# 4G.net
KiCad netlist of a schematic drawn in Altium Designer
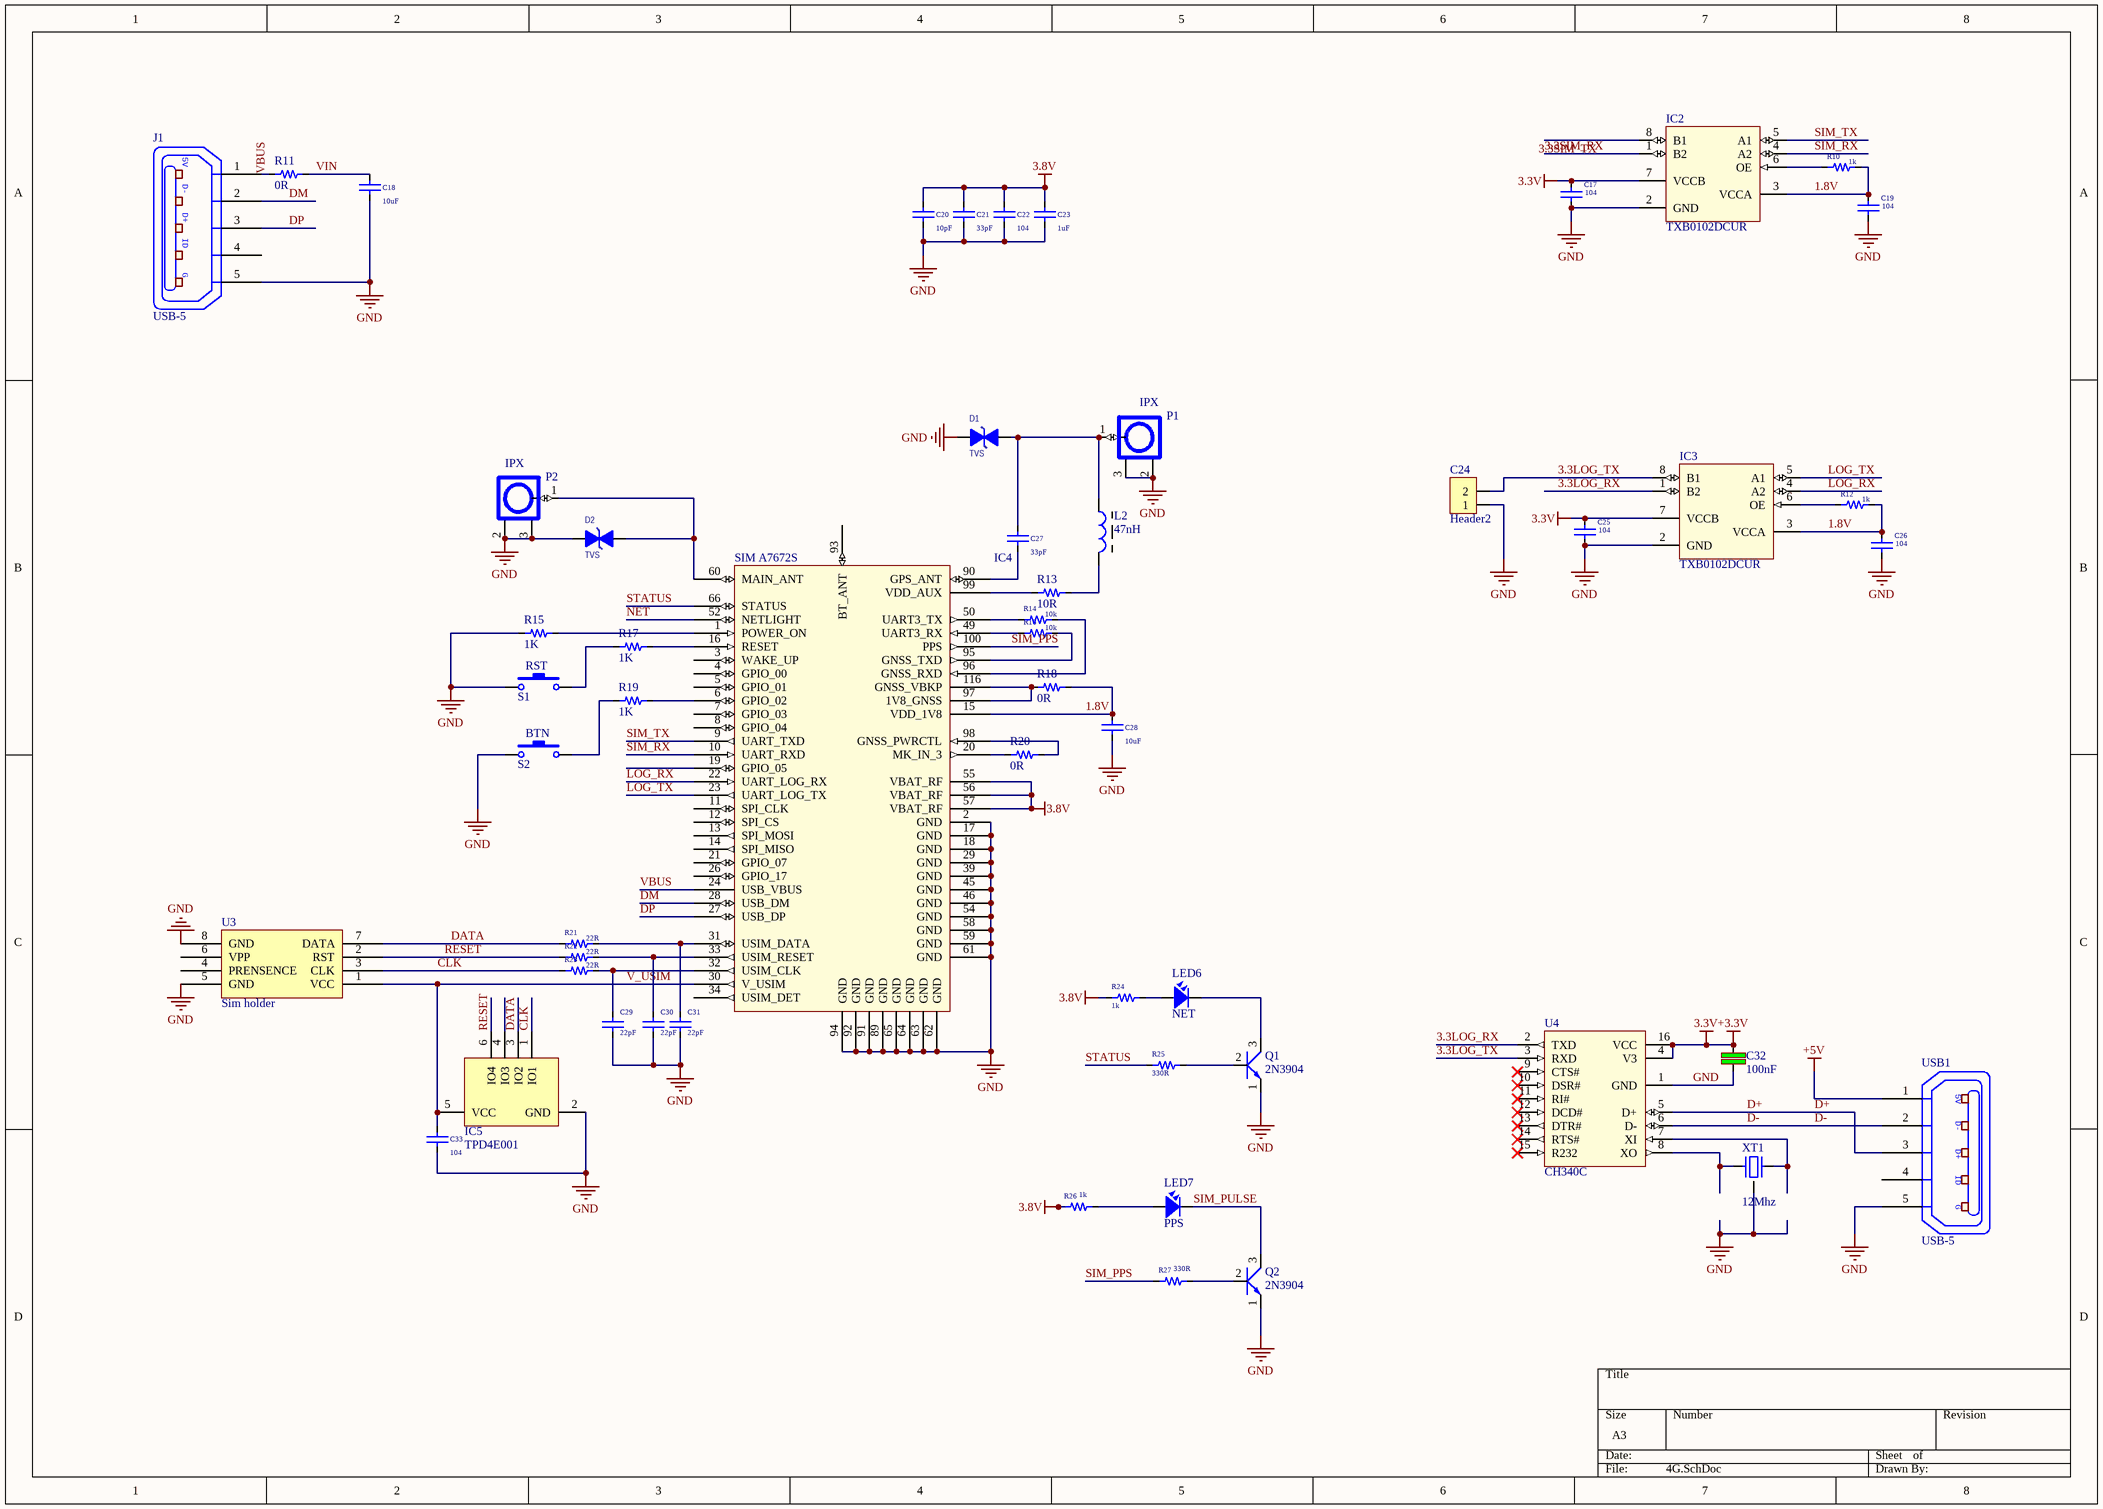
[diagram p0: 4G.SchDoc]

(export (version "E")
  (design (tool "Eeschema 10.0.6"))
  (components
    (comp (ref "C17")
      (value "104")
      (footprint "CAP_0603")
      (description "Capacitor")
      (fields (field (name "PUBLISHER") "Altium Limited"))
      (libsource (lib "My Library") (part "CapSMD"))
    )
    (comp (ref "C18")
      (value "10uF")
      (footprint "CAP_0603")
      (description "Capacitor")
      (fields (field (name "PUBLISHER") "Altium Limited"))
      (libsource (lib "My Library") (part "CapSMD"))
    )
    (comp (ref "C19")
      (value "104")
      (footprint "CAP_0603")
      (description "Capacitor")
      (fields (field (name "PUBLISHER") "Altium Limited"))
      (libsource (lib "My Library") (part "CapSMD"))
    )
    (comp (ref "C20")
      (value "10pF")
      (footprint "CAP_0603")
      (description "Capacitor")
      (fields (field (name "PUBLISHER") "Altium Limited"))
      (libsource (lib "My Library") (part "CapSMD"))
    )
    (comp (ref "C21")
      (value "33pF")
      (footprint "CAP_0603")
      (description "Capacitor")
      (fields (field (name "PUBLISHER") "Altium Limited"))
      (libsource (lib "My Library") (part "CapSMD"))
    )
    (comp (ref "C22")
      (value "104")
      (footprint "CAP_0603")
      (description "Capacitor")
      (fields (field (name "PUBLISHER") "Altium Limited"))
      (libsource (lib "My Library") (part "CapSMD"))
    )
    (comp (ref "C23")
      (value "1uF")
      (footprint "CAP_0603")
      (description "Capacitor")
      (fields (field (name "PUBLISHER") "Altium Limited"))
      (libsource (lib "My Library") (part "CapSMD"))
    )
    (comp (ref "C24")
      (value "Header2")
      (footprint "JP2")
      (description "Header IDC, 2 x 1 Pin Vertical 2.54mm Pitch (Non-Boxed, Male)")
      (fields
        (field (name "MANUFACTURER") "Würth Elektronik eiSos GmbH")
        (field (name "PARTNO") "613002143121")
        (field (name "CREATED BY") "Karrer Zheng")
      )
      (libsource (lib "My Library") (part "Header2"))
    )
    (comp (ref "C25")
      (value "104")
      (footprint "CAP_0603")
      (description "Capacitor")
      (fields (field (name "PUBLISHER") "Altium Limited"))
      (libsource (lib "My Library") (part "CapSMD"))
    )
    (comp (ref "C26")
      (value "104")
      (footprint "CAP_0603")
      (description "Capacitor")
      (fields (field (name "PUBLISHER") "Altium Limited"))
      (libsource (lib "My Library") (part "CapSMD"))
    )
    (comp (ref "C27")
      (value "33pF")
      (footprint "CAP_0603")
      (description "Capacitor")
      (fields (field (name "PUBLISHER") "Altium Limited"))
      (libsource (lib "My Library") (part "CapSMD"))
    )
    (comp (ref "C28")
      (value "10uF")
      (footprint "CAP_0603")
      (description "Capacitor")
      (fields (field (name "PUBLISHER") "Altium Limited"))
      (libsource (lib "My Library") (part "CapSMD"))
    )
    (comp (ref "C29")
      (value "22pF")
      (footprint "CAP_0603")
      (description "Capacitor")
      (fields (field (name "PUBLISHER") "Altium Limited"))
      (libsource (lib "My Library") (part "CapSMD"))
    )
    (comp (ref "C30")
      (value "22pF")
      (footprint "CAP_0603")
      (description "Capacitor")
      (fields (field (name "PUBLISHER") "Altium Limited"))
      (libsource (lib "My Library") (part "CapSMD"))
    )
    (comp (ref "C31")
      (value "22pF")
      (footprint "CAP_0603")
      (description "Capacitor")
      (fields (field (name "PUBLISHER") "Altium Limited"))
      (libsource (lib "My Library") (part "CapSMD"))
    )
    (comp (ref "C32")
      (value "100nF")
      (footprint "C-0805")
      (description "Cap SMD")
      (fields
        (field (name "MANUFACTURER") "Samsung Electro-Mechanics")
        (field (name "PART NUMBER") "CL21B104KBCNNWC")
      )
      (libsource (lib "Anh_Trung") (part "C"))
    )
    (comp (ref "C33")
      (value "104")
      (footprint "CAP_0603")
      (description "Capacitor")
      (fields (field (name "PUBLISHER") "Altium Limited"))
      (libsource (lib "My Library") (part "CapSMD"))
    )
    (comp (ref "D1")
      (value "TVS")
      (footprint "RES-SMD-0402")
      (description "TVS DIODE 4VWM 1005")
      (fields
        (field (name "MANUFACTURER") "Murata Electronics")
        (field (name "PART NUMBER") "LXES15AAA1-153")
      )
      (libsource (lib "My Library") (part "TVS"))
    )
    (comp (ref "D2")
      (value "TVS")
      (footprint "RES-SMD-0402")
      (description "TVS DIODE 4VWM 1005")
      (fields
        (field (name "MANUFACTURER") "Murata Electronics")
        (field (name "PART NUMBER") "LXES15AAA1-153")
      )
      (libsource (lib "My Library") (part "TVS"))
    )
    (comp (ref "IC2")
      (value "TXB0102DCUR")
      (footprint "TXB0102DCUR")
      (description "IC TRNSLTR BIDIRECTIONAL US8")
      (fields (field (name "MANUFACTURER") "Texas Instruments"))
      (libsource (lib "My Library") (part "TXB0102DCUR"))
    )
    (comp (ref "IC3")
      (value "TXB0102DCUR")
      (footprint "TXB0102DCUR")
      (description "IC TRNSLTR BIDIRECTIONAL US8")
      (fields (field (name "MANUFACTURER") "Texas Instruments"))
      (libsource (lib "My Library") (part "TXB0102DCUR"))
    )
    (comp (ref "IC4")
      (value "SIM A7672S")
      (footprint "A7672S")
      (description "SIM A7672S-CAT-M1")
      (libsource (lib "My Library") (part "SIM A7672S"))
    )
    (comp (ref "IC5")
      (value "TPD4E001")
      (footprint "TPD4E001")
      (fields (field (name "MANUFACTURER") "Texas Instruments") (field (name "PART NUMBER") "TPD4E001RDBVR"))
      (libsource (lib "My Library") (part "TPD4E001_1"))
    )
    (comp (ref "J1")
      (value "USB-5")
      (footprint "USB-M1")
      (fields (field (name "MANUFACTURER") "FCI"))
      (libsource (lib "Anh_Trung") (part "USB-5"))
    )
    (comp (ref "L2")
      (value "47nH")
      (footprint "RES-SMD-0603")
      (description "FIXED IND 47NH 300MA 700MOHM SMD")
      (fields (field (name "MANUFACTURER") "Taiyo Yuden") (field (name "PART NUMBER") "HK160847NJ-T"))
      (libsource (lib "Anh_Trung") (part "Inductor Ferit"))
    )
    (comp (ref "LED6")
      (value "NET")
      (footprint "LED-0805-Blue")
      (description "LED Single colour Green and Red")
      (libsource (lib "Main") (part "LED"))
    )
    (comp (ref "LED7")
      (value "PPS")
      (footprint "LED-0805-Blue")
      (description "LED Single colour Green and Red")
      (libsource (lib "Main") (part "LED"))
    )
    (comp (ref "P1")
      (value "IPX")
      (footprint "IPXS")
      (description "Antenna GSM GPS")
      (fields
        (field (name "MANUFACTURER") "TE Connectivity AMP Connectors")
        (field (name "PART NUMBER") "2334884-1")
      )
      (libsource (lib "Anh_Trung") (part "IPXSx66"))
    )
    (comp (ref "P2")
      (value "IPX")
      (footprint "IPXS")
      (description "Antenna GSM GPS")
      (fields
        (field (name "MANUFACTURER") "TE Connectivity AMP Connectors")
        (field (name "PART NUMBER") "2334884-1")
      )
      (libsource (lib "") (part "IPXSx66_1"))
    )
    (comp (ref "Q1")
      (value "2N3904")
      (footprint "SOT23C")
      (description "NPN 600mW, ECB")
      (libsource (lib "Main") (part "2N904"))
    )
    (comp (ref "Q2")
      (value "2N3904")
      (footprint "SOT23C")
      (description "NPN 600mW, ECB")
      (libsource (lib "Main") (part "2N904"))
    )
    (comp (ref "R10")
      (value "1k")
      (footprint "RES-SMD-0603")
      (description "Resistor")
      (fields
        (field (name "MANUFACTURER") "Generic Components")
        (field (name "PUBLISHER") "Altium Hobart Technology Centre")
      )
      (libsource (lib "My Library") (part "Resistor - SMD"))
    )
    (comp (ref "R11")
      (value "0R")
      (footprint "RES-SMD-0603")
      (description "Resistor")
      (fields
        (field (name "MANUFACTURER") "Generic Components")
        (field (name "PUBLISHER") "Altium Hobart Technology Centre")
      )
      (libsource (lib "My Library") (part "Resistor - SMD"))
    )
    (comp (ref "R12")
      (value "1k")
      (footprint "RES-SMD-0603")
      (description "Resistor")
      (fields
        (field (name "MANUFACTURER") "Generic Components")
        (field (name "PUBLISHER") "Altium Hobart Technology Centre")
      )
      (libsource (lib "My Library") (part "Resistor - SMD"))
    )
    (comp (ref "R13")
      (value "10R")
      (footprint "RES-SMD-0603")
      (description "Resistor")
      (fields
        (field (name "MANUFACTURER") "Generic Components")
        (field (name "PUBLISHER") "Altium Hobart Technology Centre")
      )
      (libsource (lib "My Library") (part "Resistor - SMD"))
    )
    (comp (ref "R14")
      (value "10k")
      (footprint "RES-SMD-0603")
      (description "Resistor")
      (fields
        (field (name "MANUFACTURER") "Generic Components")
        (field (name "PUBLISHER") "Altium Hobart Technology Centre")
      )
      (libsource (lib "My Library") (part "Resistor - SMD"))
    )
    (comp (ref "R15")
      (value "1K")
      (footprint "RES-SMD-0603")
      (description "Resistor")
      (fields
        (field (name "MANUFACTURER") "Generic Components")
        (field (name "PUBLISHER") "Altium Hobart Technology Centre")
      )
      (libsource (lib "My Library") (part "Resistor - SMD"))
    )
    (comp (ref "R16")
      (value "10k")
      (footprint "RES-SMD-0603")
      (description "Resistor")
      (fields
        (field (name "MANUFACTURER") "Generic Components")
        (field (name "PUBLISHER") "Altium Hobart Technology Centre")
      )
      (libsource (lib "My Library") (part "Resistor - SMD"))
    )
    (comp (ref "R17")
      (value "1K")
      (footprint "RES-SMD-0603")
      (description "Resistor")
      (fields
        (field (name "MANUFACTURER") "Generic Components")
        (field (name "PUBLISHER") "Altium Hobart Technology Centre")
      )
      (libsource (lib "My Library") (part "Resistor - SMD"))
    )
    (comp (ref "R18")
      (value "0R")
      (footprint "RES-SMD-0603")
      (description "Resistor")
      (fields
        (field (name "MANUFACTURER") "Generic Components")
        (field (name "PUBLISHER") "Altium Hobart Technology Centre")
      )
      (libsource (lib "My Library") (part "Resistor - SMD"))
    )
    (comp (ref "R19")
      (value "1K")
      (footprint "RES-SMD-0603")
      (description "Resistor")
      (fields
        (field (name "MANUFACTURER") "Generic Components")
        (field (name "PUBLISHER") "Altium Hobart Technology Centre")
      )
      (libsource (lib "My Library") (part "Resistor - SMD"))
    )
    (comp (ref "R20")
      (value "0R")
      (footprint "RES-SMD-0603")
      (description "Resistor")
      (fields
        (field (name "MANUFACTURER") "Generic Components")
        (field (name "PUBLISHER") "Altium Hobart Technology Centre")
      )
      (libsource (lib "My Library") (part "Resistor - SMD"))
    )
    (comp (ref "R21")
      (value "22R")
      (footprint "RES-SMD-0603")
      (description "Resistor")
      (fields
        (field (name "MANUFACTURER") "Generic Components")
        (field (name "PUBLISHER") "Altium Hobart Technology Centre")
      )
      (libsource (lib "My Library") (part "Resistor - SMD"))
    )
    (comp (ref "R22")
      (value "22R")
      (footprint "RES-SMD-0603")
      (description "Resistor")
      (fields
        (field (name "MANUFACTURER") "Generic Components")
        (field (name "PUBLISHER") "Altium Hobart Technology Centre")
      )
      (libsource (lib "My Library") (part "Resistor - SMD"))
    )
    (comp (ref "R23")
      (value "22R")
      (footprint "RES-SMD-0603")
      (description "Resistor")
      (fields
        (field (name "MANUFACTURER") "Generic Components")
        (field (name "PUBLISHER") "Altium Hobart Technology Centre")
      )
      (libsource (lib "My Library") (part "Resistor - SMD"))
    )
    (comp (ref "R24")
      (value "1k")
      (footprint "RES-SMD-0603")
      (description "Resistor")
      (fields
        (field (name "MANUFACTURER") "Generic Components")
        (field (name "PUBLISHER") "Altium Hobart Technology Centre")
      )
      (libsource (lib "My Library") (part "Resistor - SMD"))
    )
    (comp (ref "R25")
      (value "330R")
      (footprint "RES-SMD-0603")
      (description "Resistor")
      (fields
        (field (name "MANUFACTURER") "Generic Components")
        (field (name "PUBLISHER") "Altium Hobart Technology Centre")
      )
      (libsource (lib "My Library") (part "Resistor - SMD"))
    )
    (comp (ref "R26")
      (value "1k")
      (footprint "RES-SMD-0603")
      (description "Resistor")
      (fields
        (field (name "MANUFACTURER") "Generic Components")
        (field (name "PUBLISHER") "Altium Hobart Technology Centre")
      )
      (libsource (lib "My Library") (part "Resistor - SMD"))
    )
    (comp (ref "R27")
      (value "330R")
      (footprint "RES-SMD-0603")
      (description "Resistor")
      (fields
        (field (name "MANUFACTURER") "Generic Components")
        (field (name "PUBLISHER") "Altium Hobart Technology Centre")
      )
      (libsource (lib "My Library") (part "Resistor - SMD"))
    )
    (comp (ref "S1")
      (value "RST")
      (footprint "SW-SMD")
      (description "Switch")
      (fields (field (name "PUBLISHER") "Altium Limited"))
      (libsource (lib "My Library") (part "SW-SMD"))
    )
    (comp (ref "S2")
      (value "BTN")
      (footprint "SW-SMD")
      (description "Switch")
      (fields (field (name "PUBLISHER") "Altium Limited"))
      (libsource (lib "My Library") (part "SW-SMD"))
    )
    (comp (ref "U3")
      (value "Sim holder")
      (footprint "sim_holder_micro")
      (libsource (lib "Anh_Trung") (part "Component_1"))
    )
    (comp (ref "U4")
      (value "CH340C")
      (footprint "SOP-16")
      (description "USB to UART Interface")
      (fields (field (name "MANUFACTURER") "WCH") (field (name "PART NUMBER") "CH340G"))
      (libsource (lib "Anh_Trung") (part "CH340G"))
    )
    (comp (ref "USB1")
      (value "USB-5")
      (footprint "USB-M1")
      (fields (field (name "MANUFACTURER") "FCI"))
      (libsource (lib "") (part "USB-5_1"))
    )
    (comp (ref "XT1")
      (value "12Mhz")
      (footprint "XT32-3")
      (description "Crystal 32,768kHz for timer real")
      (libsource (lib "Anh_Trung") (part "XT32k"))
    )
  )
  (nets
    (net (code "1") (name "+3.3V") (class "Default")
      (node (ref "C17") (pin "2") (pinfunction "2_2") (pintype "passive"))
      (node (ref "C25") (pin "2") (pinfunction "2_2") (pintype "passive"))
      (node (ref "C32") (pin "2") (pinfunction "2_2") (pintype "passive"))
      (node (ref "IC2") (pin "7") (pinfunction "VCCB_7") (pintype "power_in"))
      (node (ref "IC3") (pin "7") (pinfunction "VCCB_7") (pintype "power_in"))
      (node (ref "U4") (pin "16") (pinfunction "VCC_16") (pintype "power_in"))
      (node (ref "U4") (pin "4") (pinfunction "V3_4") (pintype "passive"))
    )
    (net (code "2") (name "+5V") (class "Default")
      (node (ref "USB1") (pin "1") (pinfunction "P1_1") (pintype "passive"))
    )
    (net (code "3") (name "/1.8V") (class "Default")
      (node (ref "C19") (pin "2") (pinfunction "2_2") (pintype "passive"))
      (node (ref "C26") (pin "2") (pinfunction "2_2") (pintype "passive"))
      (node (ref "C28") (pin "2") (pinfunction "2_2") (pintype "passive"))
      (node (ref "IC2") (pin "3") (pinfunction "VCCA_3") (pintype "power_in"))
      (node (ref "IC3") (pin "3") (pinfunction "VCCA_3") (pintype "power_in"))
      (node (ref "IC4") (pin "15") (pinfunction "VDD_1V8_15") (pintype "passive"))
      (node (ref "R10") (pin "1") (pinfunction "1_1") (pintype "passive"))
      (node (ref "R12") (pin "1") (pinfunction "1_1") (pintype "passive"))
      (node (ref "R18") (pin "2") (pinfunction "2_2") (pintype "passive"))
    )
    (net (code "4") (name "/3.3LOG_RX") (class "Default")
      (node (ref "IC3") (pin "1") (pinfunction "B2_1") (pintype "bidirectional"))
      (node (ref "U4") (pin "2") (pinfunction "TXD_2") (pintype "output"))
    )
    (net (code "5") (name "/3.3LOG_TX") (class "Default")
      (node (ref "C24") (pin "2") (pinfunction "2_2") (pintype "passive"))
      (node (ref "IC3") (pin "8") (pinfunction "B1_8") (pintype "bidirectional"))
      (node (ref "U4") (pin "3") (pinfunction "RXD_3") (pintype "input"))
    )
    (net (code "6") (name "/3.3SIM_RX") (class "Default")
      (node (ref "IC2") (pin "1") (pinfunction "B2_1") (pintype "bidirectional"))
    )
    (net (code "7") (name "/3.3SIM_TX") (class "Default")
      (node (ref "IC2") (pin "8") (pinfunction "B1_8") (pintype "bidirectional"))
    )
    (net (code "8") (name "/CLK") (class "Default")
      (node (ref "IC5") (pin "1") (pinfunction "IO1_1") (pintype "passive"))
      (node (ref "R23") (pin "2") (pinfunction "2_2") (pintype "passive"))
      (node (ref "U3") (pin "3") (pinfunction "CLK_3") (pintype "passive"))
    )
    (net (code "9") (name "/D+") (class "Default")
      (node (ref "U4") (pin "5") (pinfunction "D+_5") (pintype "bidirectional"))
      (node (ref "USB1") (pin "3") (pinfunction "P3_3") (pintype "passive"))
    )
    (net (code "10") (name "/D-") (class "Default")
      (node (ref "U4") (pin "6") (pinfunction "D-_6") (pintype "bidirectional"))
      (node (ref "USB1") (pin "2") (pinfunction "P2_2") (pintype "passive"))
    )
    (net (code "11") (name "/DATA") (class "Default")
      (node (ref "IC5") (pin "3") (pinfunction "IO2_3") (pintype "passive"))
      (node (ref "R21") (pin "2") (pinfunction "2_2") (pintype "passive"))
      (node (ref "U3") (pin "7") (pinfunction "DATA_7") (pintype "passive"))
    )
    (net (code "12") (name "/DM") (class "Default")
      (node (ref "IC4") (pin "28") (pinfunction "USB_DM_28") (pintype "bidirectional"))
      (node (ref "J1") (pin "2") (pinfunction "P2_2") (pintype "passive"))
    )
    (net (code "13") (name "/DP") (class "Default")
      (node (ref "IC4") (pin "27") (pinfunction "USB_DP_27") (pintype "bidirectional"))
      (node (ref "J1") (pin "3") (pinfunction "P3_3") (pintype "passive"))
    )
    (net (code "14") (name "/LOG_RX") (class "Default")
      (node (ref "IC3") (pin "4") (pinfunction "A2_4") (pintype "bidirectional"))
      (node (ref "IC4") (pin "22") (pinfunction "UART_LOG_RX_22") (pintype "input"))
    )
    (net (code "15") (name "/LOG_TX") (class "Default")
      (node (ref "IC3") (pin "5") (pinfunction "A1_5") (pintype "bidirectional"))
      (node (ref "IC4") (pin "23") (pinfunction "UART_LOG_TX_23") (pintype "output"))
    )
    (net (code "16") (name "/NET") (class "Default")
      (node (ref "IC4") (pin "52") (pinfunction "NETLIGHT_52") (pintype "bidirectional"))
    )
    (net (code "17") (name "/RESET") (class "Default")
      (node (ref "IC5") (pin "6") (pinfunction "IO4_6") (pintype "passive"))
      (node (ref "R22") (pin "2") (pinfunction "2_2") (pintype "passive"))
      (node (ref "U3") (pin "2") (pinfunction "RST_2") (pintype "passive"))
    )
    (net (code "18") (name "/SIM_PPS") (class "Default")
      (node (ref "IC4") (pin "100") (pinfunction "PPS_100") (pintype "output"))
      (node (ref "R27") (pin "2") (pinfunction "2_2") (pintype "passive"))
    )
    (net (code "19") (name "/SIM_PULSE") (class "Default")
      (node (ref "LED7") (pin "2") (pinfunction "2_2") (pintype "passive"))
      (node (ref "Q2") (pin "3") (pinfunction "C_3") (pintype "passive"))
    )
    (net (code "20") (name "/SIM_RX") (class "Default")
      (node (ref "IC2") (pin "4") (pinfunction "A2_4") (pintype "bidirectional"))
      (node (ref "IC4") (pin "10") (pinfunction "UART_RXD_10") (pintype "input"))
    )
    (net (code "21") (name "/SIM_TX") (class "Default")
      (node (ref "IC2") (pin "5") (pinfunction "A1_5") (pintype "bidirectional"))
      (node (ref "IC4") (pin "9") (pinfunction "UART_TXD_9") (pintype "output"))
    )
    (net (code "22") (name "/STATUS") (class "Default")
      (node (ref "IC4") (pin "66") (pinfunction "STATUS_66") (pintype "bidirectional"))
      (node (ref "R25") (pin "2") (pinfunction "2_2") (pintype "passive"))
    )
    (net (code "23") (name "/VBUS") (class "Default")
      (node (ref "IC4") (pin "24") (pinfunction "USB_VBUS_24") (pintype "passive"))
      (node (ref "J1") (pin "1") (pinfunction "P1_1") (pintype "passive"))
      (node (ref "R11") (pin "1") (pinfunction "1_1") (pintype "passive"))
    )
    (net (code "24") (name "/VIN") (class "Default")
      (node (ref "C18") (pin "2") (pinfunction "2_2") (pintype "passive"))
      (node (ref "R11") (pin "2") (pinfunction "2_2") (pintype "passive"))
    )
    (net (code "25") (name "/V_USIM") (class "Default")
      (node (ref "C33") (pin "2") (pinfunction "2_2") (pintype "passive"))
      (node (ref "IC4") (pin "30") (pinfunction "V_USIM_30") (pintype "output"))
      (node (ref "IC5") (pin "5") (pinfunction "VCC_5") (pintype "passive"))
      (node (ref "U3") (pin "1") (pinfunction "VCC_1") (pintype "passive"))
    )
    (net (code "26") (name "3.8V") (class "Default")
      (node (ref "C20") (pin "2") (pinfunction "2_2") (pintype "passive"))
      (node (ref "C21") (pin "2") (pinfunction "2_2") (pintype "passive"))
      (node (ref "C22") (pin "2") (pinfunction "2_2") (pintype "passive"))
      (node (ref "C23") (pin "2") (pinfunction "2_2") (pintype "passive"))
      (node (ref "IC4") (pin "55") (pinfunction "VBAT_RF_55") (pintype "passive"))
      (node (ref "IC4") (pin "56") (pinfunction "VBAT_RF_56") (pintype "passive"))
      (node (ref "IC4") (pin "57") (pinfunction "VBAT_RF_57") (pintype "passive"))
      (node (ref "R24") (pin "2") (pinfunction "2_2") (pintype "passive"))
      (node (ref "R26") (pin "2") (pinfunction "2_2") (pintype "passive"))
    )
    (net (code "27") (name "GND") (class "Default")
      (node (ref "C17") (pin "1") (pinfunction "1_1") (pintype "passive"))
      (node (ref "C18") (pin "1") (pinfunction "1_1") (pintype "passive"))
      (node (ref "C19") (pin "1") (pinfunction "1_1") (pintype "passive"))
      (node (ref "C20") (pin "1") (pinfunction "1_1") (pintype "passive"))
      (node (ref "C21") (pin "1") (pinfunction "1_1") (pintype "passive"))
      (node (ref "C22") (pin "1") (pinfunction "1_1") (pintype "passive"))
      (node (ref "C23") (pin "1") (pinfunction "1_1") (pintype "passive"))
      (node (ref "C24") (pin "1") (pinfunction "1_1") (pintype "passive"))
      (node (ref "C25") (pin "1") (pinfunction "1_1") (pintype "passive"))
      (node (ref "C26") (pin "1") (pinfunction "1_1") (pintype "passive"))
      (node (ref "C28") (pin "1") (pinfunction "1_1") (pintype "passive"))
      (node (ref "C29") (pin "1") (pinfunction "1_1") (pintype "passive"))
      (node (ref "C30") (pin "1") (pinfunction "1_1") (pintype "passive"))
      (node (ref "C31") (pin "1") (pinfunction "1_1") (pintype "passive"))
      (node (ref "C32") (pin "1") (pinfunction "1_1") (pintype "passive"))
      (node (ref "C33") (pin "1") (pinfunction "1_1") (pintype "passive"))
      (node (ref "D1") (pin "2") (pinfunction "K_2") (pintype "passive"))
      (node (ref "D2") (pin "2") (pinfunction "K_2") (pintype "passive"))
      (node (ref "IC2") (pin "2") (pinfunction "GND_2") (pintype "power_in"))
      (node (ref "IC3") (pin "2") (pinfunction "GND_2") (pintype "power_in"))
      (node (ref "IC4") (pin "17") (pinfunction "GND_17") (pintype "passive"))
      (node (ref "IC4") (pin "18") (pinfunction "GND_18") (pintype "passive"))
      (node (ref "IC4") (pin "2") (pinfunction "GND_2") (pintype "passive"))
      (node (ref "IC4") (pin "29") (pinfunction "GND_29") (pintype "passive"))
      (node (ref "IC4") (pin "39") (pinfunction "GND_39") (pintype "passive"))
      (node (ref "IC4") (pin "45") (pinfunction "GND_45") (pintype "passive"))
      (node (ref "IC4") (pin "46") (pinfunction "GND_46") (pintype "passive"))
      (node (ref "IC4") (pin "54") (pinfunction "GND_54") (pintype "passive"))
      (node (ref "IC4") (pin "58") (pinfunction "GND_58") (pintype "passive"))
      (node (ref "IC4") (pin "59") (pinfunction "GND_59") (pintype "passive"))
      (node (ref "IC4") (pin "61") (pinfunction "GND_61") (pintype "passive"))
      (node (ref "IC4") (pin "62") (pinfunction "GND_62") (pintype "passive"))
      (node (ref "IC4") (pin "63") (pinfunction "GND_63") (pintype "passive"))
      (node (ref "IC4") (pin "64") (pinfunction "GND_64") (pintype "passive"))
      (node (ref "IC4") (pin "65") (pinfunction "GND_65") (pintype "passive"))
      (node (ref "IC4") (pin "89") (pinfunction "GND_89") (pintype "passive"))
      (node (ref "IC4") (pin "91") (pinfunction "GND_91") (pintype "passive"))
      (node (ref "IC4") (pin "92") (pinfunction "GND_92") (pintype "passive"))
      (node (ref "IC4") (pin "94") (pinfunction "GND_94") (pintype "passive"))
      (node (ref "IC5") (pin "2") (pinfunction "GND_2") (pintype "passive"))
      (node (ref "J1") (pin "5") (pinfunction "P5_5") (pintype "passive"))
      (node (ref "P1") (pin "2") (pintype "passive"))
      (node (ref "P1") (pin "3") (pintype "passive"))
      (node (ref "P2") (pin "2") (pintype "passive"))
      (node (ref "P2") (pin "3") (pintype "passive"))
      (node (ref "Q1") (pin "1") (pinfunction "E_1") (pintype "passive"))
      (node (ref "Q2") (pin "1") (pinfunction "E_1") (pintype "passive"))
      (node (ref "R15") (pin "1") (pinfunction "1_1") (pintype "passive"))
      (node (ref "S1") (pin "1") (pinfunction "1_1") (pintype "passive"))
      (node (ref "S2") (pin "1") (pinfunction "1_1") (pintype "passive"))
      (node (ref "U3") (pin "5") (pinfunction "GND_5") (pintype "passive"))
      (node (ref "U3") (pin "8") (pinfunction "GND_8") (pintype "passive"))
      (node (ref "U4") (pin "1") (pinfunction "GND_1") (pintype "passive"))
      (node (ref "USB1") (pin "5") (pinfunction "P5_5") (pintype "passive"))
      (node (ref "XT1") (pin "3") (pinfunction "3_3") (pintype "passive"))
    )
    (net (code "28") (name "Net-(D1-A)") (class "Default")
      (node (ref "C27") (pin "2") (pinfunction "2_2") (pintype "passive"))
      (node (ref "D1") (pin "1") (pinfunction "A_1") (pintype "passive"))
      (node (ref "L2") (pin "1") (pinfunction "1_1") (pintype "passive"))
      (node (ref "P1") (pin "1") (pintype "bidirectional"))
    )
    (net (code "29") (name "Net-(D2-A)") (class "Default")
      (node (ref "D2") (pin "1") (pinfunction "A_1") (pintype "passive"))
      (node (ref "IC4") (pin "60") (pinfunction "MAIN_ANT_60") (pintype "bidirectional"))
      (node (ref "P2") (pin "1") (pintype "bidirectional"))
    )
    (net (code "30") (name "Net-(IC2-OE)") (class "Default")
      (node (ref "IC2") (pin "6") (pinfunction "OE_6") (pintype "input"))
      (node (ref "R10") (pin "2") (pinfunction "2_2") (pintype "passive"))
    )
    (net (code "31") (name "Net-(IC3-OE)") (class "Default")
      (node (ref "IC3") (pin "6") (pinfunction "OE_6") (pintype "input"))
      (node (ref "R12") (pin "2") (pinfunction "2_2") (pintype "passive"))
    )
    (net (code "32") (name "Net-(IC4-1V8_GNSS)") (class "Default")
      (node (ref "IC4") (pin "116") (pinfunction "GNSS_VBKP_116") (pintype "passive"))
      (node (ref "IC4") (pin "97") (pinfunction "1V8_GNSS_97") (pintype "passive"))
      (node (ref "R18") (pin "1") (pinfunction "1_1") (pintype "passive"))
    )
    (net (code "33") (name "Net-(IC4-GNSS_PWRCTL)") (class "Default")
      (node (ref "IC4") (pin "98") (pinfunction "GNSS_PWRCTL_98") (pintype "input"))
      (node (ref "R20") (pin "2") (pinfunction "2_2") (pintype "passive"))
    )
    (net (code "34") (name "Net-(IC4-GNSS_RXD)") (class "Default")
      (node (ref "IC4") (pin "96") (pinfunction "GNSS_RXD_96") (pintype "input"))
      (node (ref "R14") (pin "1") (pinfunction "1_1") (pintype "passive"))
    )
    (net (code "35") (name "Net-(IC4-GNSS_TXD)") (class "Default")
      (node (ref "IC4") (pin "95") (pinfunction "GNSS_TXD_95") (pintype "output"))
      (node (ref "R16") (pin "1") (pinfunction "1_1") (pintype "passive"))
    )
    (net (code "36") (name "Net-(IC4-GPIO_02)") (class "Default")
      (node (ref "IC4") (pin "6") (pinfunction "GPIO_02_6") (pintype "bidirectional"))
      (node (ref "R19") (pin "1") (pinfunction "1_1") (pintype "passive"))
    )
    (net (code "37") (name "Net-(IC4-GPS_ANT)") (class "Default")
      (node (ref "C27") (pin "1") (pinfunction "1_1") (pintype "passive"))
      (node (ref "IC4") (pin "90") (pinfunction "GPS_ANT_90") (pintype "bidirectional"))
    )
    (net (code "38") (name "Net-(IC4-MK_IN_3)") (class "Default")
      (node (ref "IC4") (pin "20") (pinfunction "MK_IN_3_20") (pintype "output"))
      (node (ref "R20") (pin "1") (pinfunction "1_1") (pintype "passive"))
    )
    (net (code "39") (name "Net-(IC4-POWER_ON)") (class "Default")
      (node (ref "IC4") (pin "1") (pinfunction "POWER_ON_1") (pintype "input"))
      (node (ref "R15") (pin "2") (pinfunction "2_2") (pintype "passive"))
    )
    (net (code "40") (name "Net-(IC4-RESET)") (class "Default")
      (node (ref "IC4") (pin "16") (pinfunction "RESET_16") (pintype "input"))
      (node (ref "R17") (pin "2") (pinfunction "2_2") (pintype "passive"))
    )
    (net (code "41") (name "Net-(IC4-UART3_RX)") (class "Default")
      (node (ref "IC4") (pin "49") (pinfunction "UART3_RX_49") (pintype "input"))
      (node (ref "R16") (pin "2") (pinfunction "2_2") (pintype "passive"))
    )
    (net (code "42") (name "Net-(IC4-UART3_TX)") (class "Default")
      (node (ref "IC4") (pin "50") (pinfunction "UART3_TX_50") (pintype "output"))
      (node (ref "R14") (pin "2") (pinfunction "2_2") (pintype "passive"))
    )
    (net (code "43") (name "Net-(IC4-USIM_CLK)") (class "Default")
      (node (ref "C29") (pin "2") (pinfunction "2_2") (pintype "passive"))
      (node (ref "IC4") (pin "32") (pinfunction "USIM_CLK_32") (pintype "output"))
      (node (ref "R23") (pin "1") (pinfunction "1_1") (pintype "passive"))
    )
    (net (code "44") (name "Net-(IC4-USIM_DATA)") (class "Default")
      (node (ref "C31") (pin "2") (pinfunction "2_2") (pintype "passive"))
      (node (ref "IC4") (pin "31") (pinfunction "USIM_DATA_31") (pintype "bidirectional"))
      (node (ref "R21") (pin "1") (pinfunction "1_1") (pintype "passive"))
    )
    (net (code "45") (name "Net-(IC4-USIM_RESET)") (class "Default")
      (node (ref "C30") (pin "2") (pinfunction "2_2") (pintype "passive"))
      (node (ref "IC4") (pin "33") (pinfunction "USIM_RESET_33") (pintype "output"))
      (node (ref "R22") (pin "1") (pinfunction "1_1") (pintype "passive"))
    )
    (net (code "46") (name "Net-(IC4-VDD_AUX)") (class "Default")
      (node (ref "IC4") (pin "99") (pinfunction "VDD_AUX_99") (pintype "passive"))
      (node (ref "R13") (pin "1") (pinfunction "1_1") (pintype "passive"))
    )
    (net (code "47") (name "Net-(L2-Pad2)") (class "Default")
      (node (ref "L2") (pin "2") (pinfunction "2_2") (pintype "passive"))
      (node (ref "R13") (pin "2") (pinfunction "2_2") (pintype "passive"))
    )
    (net (code "48") (name "Net-(LED6-Pad1)") (class "Default")
      (node (ref "LED6") (pin "1") (pinfunction "1_1") (pintype "passive"))
      (node (ref "R24") (pin "1") (pinfunction "1_1") (pintype "passive"))
    )
    (net (code "49") (name "Net-(LED7-Pad1)") (class "Default")
      (node (ref "LED7") (pin "1") (pinfunction "1_1") (pintype "passive"))
      (node (ref "R26") (pin "1") (pinfunction "1_1") (pintype "passive"))
    )
    (net (code "50") (name "Net-(Q1-B)") (class "Default")
      (node (ref "Q1") (pin "2") (pinfunction "B_2") (pintype "passive"))
      (node (ref "R25") (pin "1") (pinfunction "1_1") (pintype "passive"))
    )
    (net (code "51") (name "Net-(Q1-C)") (class "Default")
      (node (ref "LED6") (pin "2") (pinfunction "2_2") (pintype "passive"))
      (node (ref "Q1") (pin "3") (pinfunction "C_3") (pintype "passive"))
    )
    (net (code "52") (name "Net-(Q2-B)") (class "Default")
      (node (ref "Q2") (pin "2") (pinfunction "B_2") (pintype "passive"))
      (node (ref "R27") (pin "1") (pinfunction "1_1") (pintype "passive"))
    )
    (net (code "53") (name "Net-(R17-Pad1)") (class "Default")
      (node (ref "R17") (pin "1") (pinfunction "1_1") (pintype "passive"))
      (node (ref "S1") (pin "2") (pinfunction "2_2") (pintype "passive"))
    )
    (net (code "54") (name "Net-(R19-Pad2)") (class "Default")
      (node (ref "R19") (pin "2") (pinfunction "2_2") (pintype "passive"))
      (node (ref "S2") (pin "2") (pinfunction "2_2") (pintype "passive"))
    )
    (net (code "55") (name "Net-(U4-XI)") (class "Default")
      (node (ref "U4") (pin "7") (pinfunction "XI_7") (pintype "input"))
      (node (ref "XT1") (pin "2") (pinfunction "2_2") (pintype "passive"))
    )
    (net (code "56") (name "Net-(U4-XO)") (class "Default")
      (node (ref "U4") (pin "8") (pinfunction "XO_8") (pintype "output"))
      (node (ref "XT1") (pin "1") (pinfunction "1_1") (pintype "passive"))
    )
    (net (code "57") (name "unconnected-(IC4-ADC1-Pad47)") (class "Default")
      (node (ref "IC4") (pin "47") (pinfunction "ADC1_47") (pintype "passive"))
    )
    (net (code "58") (name "unconnected-(IC4-ADC2-Pad46)") (class "Default")
      (node (ref "IC4") (pin "46") (pinfunction "ADC2_46") (pintype "passive"))
    )
    (net (code "59") (name "unconnected-(IC4-BT_ANT-Pad93)") (class "Default")
      (node (ref "IC4") (pin "93") (pinfunction "BT_ANT_93") (pintype "bidirectional"))
    )
    (net (code "60") (name "unconnected-(IC4-EAR1N-Pad25)") (class "Default")
      (node (ref "IC4") (pin "25") (pinfunction "EAR1N_25") (pintype "passive"))
    )
    (net (code "61") (name "unconnected-(IC4-EAR1P-Pad26)") (class "Default")
      (node (ref "IC4") (pin "26") (pinfunction "EAR1P_26") (pintype "passive"))
    )
    (net (code "62") (name "unconnected-(IC4-GPIO1-Pad51)") (class "Default")
      (node (ref "IC4") (pin "51") (pinfunction "GPIO1_51") (pintype "passive"))
    )
    (net (code "63") (name "unconnected-(IC4-GPIO4-Pad54)") (class "Default")
      (node (ref "IC4") (pin "54") (pinfunction "GPIO4_54") (pintype "passive"))
    )
    (net (code "64") (name "unconnected-(IC4-GPIO40-Pad49)") (class "Default")
      (node (ref "IC4") (pin "49") (pinfunction "GPIO40_49") (pintype "passive"))
    )
    (net (code "65") (name "unconnected-(IC4-GPIO41-Pad52)") (class "Default")
      (node (ref "IC4") (pin "52") (pinfunction "GPIO41_52") (pintype "passive"))
    )
    (net (code "66") (name "unconnected-(IC4-GPIO42-Pad53)") (class "Default")
      (node (ref "IC4") (pin "53") (pinfunction "GPIO42_53") (pintype "passive"))
    )
    (net (code "67") (name "unconnected-(IC4-GPIO43-Pad50)") (class "Default")
      (node (ref "IC4") (pin "50") (pinfunction "GPIO43_50") (pintype "passive"))
    )
    (net (code "68") (name "unconnected-(IC4-GPIO44-Pad48)") (class "Default")
      (node (ref "IC4") (pin "48") (pinfunction "GPIO44_48") (pintype "passive"))
    )
    (net (code "69") (name "unconnected-(IC4-GPIO_00-Pad4)") (class "Default")
      (node (ref "IC4") (pin "4") (pinfunction "GPIO_00_4") (pintype "bidirectional"))
    )
    (net (code "70") (name "unconnected-(IC4-GPIO_01-Pad5)") (class "Default")
      (node (ref "IC4") (pin "5") (pinfunction "GPIO_01_5") (pintype "bidirectional"))
    )
    (net (code "71") (name "unconnected-(IC4-GPIO_03-Pad7)") (class "Default")
      (node (ref "IC4") (pin "7") (pinfunction "GPIO_03_7") (pintype "bidirectional"))
    )
    (net (code "72") (name "unconnected-(IC4-GPIO_04-Pad8)") (class "Default")
      (node (ref "IC4") (pin "8") (pinfunction "GPIO_04_8") (pintype "bidirectional"))
    )
    (net (code "73") (name "unconnected-(IC4-GPIO_05-Pad19)") (class "Default")
      (node (ref "IC4") (pin "19") (pinfunction "GPIO_05_19") (pintype "bidirectional"))
    )
    (net (code "74") (name "unconnected-(IC4-GPIO_07-Pad21)") (class "Default")
      (node (ref "IC4") (pin "21") (pinfunction "GPIO_07_21") (pintype "bidirectional"))
    )
    (net (code "75") (name "unconnected-(IC4-GPIO_17-Pad26)") (class "Default")
      (node (ref "IC4") (pin "26") (pinfunction "GPIO_17_26") (pintype "bidirectional"))
    )
    (net (code "76") (name "unconnected-(IC4-KEYPAD_0-Pad29)") (class "Default")
      (node (ref "IC4") (pin "29") (pinfunction "KEYPAD_0_29") (pintype "passive"))
    )
    (net (code "77") (name "unconnected-(IC4-KEYPAD_1-Pad33)") (class "Default")
      (node (ref "IC4") (pin "33") (pinfunction "KEYPAD_1_33") (pintype "passive"))
    )
    (net (code "78") (name "unconnected-(IC4-KEYPAD_2-Pad30)") (class "Default")
      (node (ref "IC4") (pin "30") (pinfunction "KEYPAD_2_30") (pintype "passive"))
    )
    (net (code "79") (name "unconnected-(IC4-KEYPAD_3-Pad35)") (class "Default")
      (node (ref "IC4") (pin "35") (pinfunction "KEYPAD_3_35") (pintype "passive"))
    )
    (net (code "80") (name "unconnected-(IC4-KEYPAD_4-Pad34)") (class "Default")
      (node (ref "IC4") (pin "34") (pinfunction "KEYPAD_4_34") (pintype "passive"))
    )
    (net (code "81") (name "unconnected-(IC4-KEYSENSE_N0-Pad28)") (class "Default")
      (node (ref "IC4") (pin "28") (pinfunction "KEYSENSE_N0_28") (pintype "passive"))
    )
    (net (code "82") (name "unconnected-(IC4-KEYSENSE_N1-Pad27)") (class "Default")
      (node (ref "IC4") (pin "27") (pinfunction "KEYSENSE_N1_27") (pintype "passive"))
    )
    (net (code "83") (name "unconnected-(IC4-KEYSENSE_N2-Pad31)") (class "Default")
      (node (ref "IC4") (pin "31") (pinfunction "KEYSENSE_N2_31") (pintype "passive"))
    )
    (net (code "84") (name "unconnected-(IC4-KEYSENSE_N3-Pad32)") (class "Default")
      (node (ref "IC4") (pin "32") (pinfunction "KEYSENSE_N3_32") (pintype "passive"))
    )
    (net (code "85") (name "unconnected-(IC4-KEYSENSE_N4-Pad36)") (class "Default")
      (node (ref "IC4") (pin "36") (pinfunction "KEYSENSE_N4_36") (pintype "passive"))
    )
    (net (code "86") (name "unconnected-(IC4-MIC1N-Pad24)") (class "Default")
      (node (ref "IC4") (pin "24") (pinfunction "MIC1N_24") (pintype "passive"))
    )
    (net (code "87") (name "unconnected-(IC4-MIC1P-Pad23)") (class "Default")
      (node (ref "IC4") (pin "23") (pinfunction "MIC1P_23") (pintype "passive"))
    )
    (net (code "88") (name "unconnected-(IC4-PCM_CLK-Pad76)") (class "Default")
      (node (ref "IC4") (pin "76") (pinfunction "PCM_CLK_76") (pintype "passive"))
    )
    (net (code "89") (name "unconnected-(IC4-PCM_DIN-Pad74)") (class "Default")
      (node (ref "IC4") (pin "74") (pinfunction "PCM_DIN_74") (pintype "passive"))
    )
    (net (code "90") (name "unconnected-(IC4-PCM_DOUT-Pad73)") (class "Default")
      (node (ref "IC4") (pin "73") (pinfunction "PCM_DOUT_73") (pintype "passive"))
    )
    (net (code "91") (name "unconnected-(IC4-PCM_SYNC-Pad75)") (class "Default")
      (node (ref "IC4") (pin "75") (pinfunction "PCM_SYNC_75") (pintype "passive"))
    )
    (net (code "92") (name "unconnected-(IC4-RESERVED-Pad15)") (class "Default")
      (node (ref "IC4") (pin "15") (pinfunction "RESERVED_15") (pintype "passive"))
    )
    (net (code "93") (name "unconnected-(IC4-RESERVED-Pad16)") (class "Default")
      (node (ref "IC4") (pin "16") (pinfunction "RESERVED_16") (pintype "passive"))
    )
    (net (code "94") (name "unconnected-(IC4-SPI_CLK-Pad11)") (class "Default")
      (node (ref "IC4") (pin "11") (pinfunction "SPI_CLK_11") (pintype "bidirectional"))
    )
    (net (code "95") (name "unconnected-(IC4-SPI_CS-Pad12)") (class "Default")
      (node (ref "IC4") (pin "12") (pinfunction "SPI_CS_12") (pintype "bidirectional"))
    )
    (net (code "96") (name "unconnected-(IC4-SPI_MISO-Pad14)") (class "Default")
      (node (ref "IC4") (pin "14") (pinfunction "SPI_MISO_14") (pintype "output"))
    )
    (net (code "97") (name "unconnected-(IC4-SPI_MOSI-Pad13)") (class "Default")
      (node (ref "IC4") (pin "13") (pinfunction "SPI_MOSI_13") (pintype "output"))
    )
    (net (code "98") (name "unconnected-(IC4-SPK_M-Pad21)") (class "Default")
      (node (ref "IC4") (pin "21") (pinfunction "SPK_M_21") (pintype "passive"))
    )
    (net (code "99") (name "unconnected-(IC4-SPK_P-Pad22)") (class "Default")
      (node (ref "IC4") (pin "22") (pinfunction "SPK_P_22") (pintype "passive"))
    )
    (net (code "100") (name "unconnected-(IC4-USIM_DET-Pad34)") (class "Default")
      (node (ref "IC4") (pin "34") (pinfunction "USIM_DET_34") (pintype "output"))
    )
    (net (code "101") (name "unconnected-(IC4-WAKE_UP-Pad3)") (class "Default")
      (node (ref "IC4") (pin "3") (pinfunction "WAKE_UP_3") (pintype "bidirectional"))
    )
    (net (code "102") (name "unconnected-(IC5-IO3-Pad4)") (class "Default")
      (node (ref "IC5") (pin "4") (pinfunction "IO3_4") (pintype "passive"))
    )
    (net (code "103") (name "unconnected-(J1-P4-Pad4)") (class "Default")
      (node (ref "J1") (pin "4") (pinfunction "P4_4") (pintype "passive"))
    )
    (net (code "104") (name "unconnected-(U3-PRENSENCE-Pad4)") (class "Default")
      (node (ref "U3") (pin "4") (pinfunction "PRENSENCE_4") (pintype "passive"))
    )
    (net (code "105") (name "unconnected-(U3-VPP-Pad6)") (class "Default")
      (node (ref "U3") (pin "6") (pinfunction "VPP_6") (pintype "passive"))
    )
    (net (code "106") (name "unconnected-(U4-CTS#-Pad9)") (class "Default")
      (node (ref "U4") (pin "9") (pinfunction "CTS#_9") (pintype "input+no_connect"))
    )
    (net (code "107") (name "unconnected-(U4-DCD#-Pad12)") (class "Default")
      (node (ref "U4") (pin "12") (pinfunction "DCD#_12") (pintype "input+no_connect"))
    )
    (net (code "108") (name "unconnected-(U4-DSR#-Pad10)") (class "Default")
      (node (ref "U4") (pin "10") (pinfunction "DSR#_10") (pintype "input+no_connect"))
    )
    (net (code "109") (name "unconnected-(U4-DTR#-Pad13)") (class "Default")
      (node (ref "U4") (pin "13") (pinfunction "DTR#_13") (pintype "output+no_connect"))
    )
    (net (code "110") (name "unconnected-(U4-R232-Pad15)") (class "Default")
      (node (ref "U4") (pin "15") (pinfunction "R232_15") (pintype "input+no_connect"))
    )
    (net (code "111") (name "unconnected-(U4-RI#-Pad11)") (class "Default")
      (node (ref "U4") (pin "11") (pinfunction "RI#_11") (pintype "input+no_connect"))
    )
    (net (code "112") (name "unconnected-(U4-RTS#-Pad14)") (class "Default")
      (node (ref "U4") (pin "14") (pinfunction "RTS#_14") (pintype "output+no_connect"))
    )
    (net (code "113") (name "unconnected-(USB1-P4-Pad4)") (class "Default")
      (node (ref "USB1") (pin "4") (pinfunction "P4_4") (pintype "passive"))
    )
  )
)
